# KN-CON.net
KiCad netlist of a schematic drawn in EAGLE
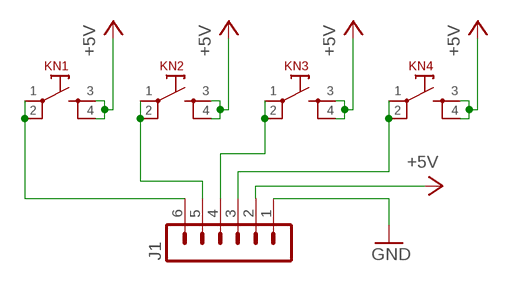
[diagram p0: schematic, sheet 1]

(export (version "E")
  (design (tool "Eeschema 10.0.6"))
  (components
    (comp (ref "J1")
      (value "MA06-1")
      (footprint "eagle-import:MA06-1")
      (libsource (lib "eagle-import") (part "MA06-1"))
    )
    (comp (ref "KN1")
      (value "LZQ-KN")
      (footprint "eagle-import:LZQ-KN")
      (libsource (lib "eagle-import") (part "LZQ-KN"))
    )
    (comp (ref "KN2")
      (value "LZQ-KN")
      (footprint "eagle-import:LZQ-KN")
      (libsource (lib "eagle-import") (part "LZQ-KN"))
    )
    (comp (ref "KN3")
      (value "LZQ-KN")
      (footprint "eagle-import:LZQ-KN")
      (libsource (lib "eagle-import") (part "LZQ-KN"))
    )
    (comp (ref "KN4")
      (value "LZQ-KN")
      (footprint "eagle-import:LZQ-KN")
      (libsource (lib "eagle-import") (part "LZQ-KN"))
    )
  )
  (nets
    (net (code "1") (name "+5V") (class "Default")
      (node (ref "J1") (pin "2") (pinfunction "2_2") (pintype "passive"))
      (node (ref "KN1") (pin "3") (pinfunction "3_3") (pintype "bidirectional"))
      (node (ref "KN1") (pin "4") (pinfunction "4_4") (pintype "bidirectional"))
      (node (ref "KN2") (pin "3") (pinfunction "3_3") (pintype "bidirectional"))
      (node (ref "KN2") (pin "4") (pinfunction "4_4") (pintype "bidirectional"))
      (node (ref "KN3") (pin "3") (pinfunction "3_3") (pintype "bidirectional"))
      (node (ref "KN3") (pin "4") (pinfunction "4_4") (pintype "bidirectional"))
      (node (ref "KN4") (pin "3") (pinfunction "3_3") (pintype "bidirectional"))
      (node (ref "KN4") (pin "4") (pinfunction "4_4") (pintype "bidirectional"))
    )
    (net (code "2") (name "GND") (class "Default")
      (node (ref "J1") (pin "1") (pinfunction "1_1") (pintype "passive"))
    )
    (net (code "3") (name "Net-(J1-Pad3)") (class "Default")
      (node (ref "J1") (pin "3") (pinfunction "3_3") (pintype "passive"))
      (node (ref "KN4") (pin "1") (pinfunction "1_1") (pintype "bidirectional"))
      (node (ref "KN4") (pin "2") (pinfunction "2_2") (pintype "bidirectional"))
    )
    (net (code "4") (name "Net-(J1-Pad4)") (class "Default")
      (node (ref "J1") (pin "4") (pinfunction "4_4") (pintype "passive"))
      (node (ref "KN3") (pin "1") (pinfunction "1_1") (pintype "bidirectional"))
      (node (ref "KN3") (pin "2") (pinfunction "2_2") (pintype "bidirectional"))
    )
    (net (code "5") (name "Net-(J1-Pad5)") (class "Default")
      (node (ref "J1") (pin "5") (pinfunction "5_5") (pintype "passive"))
      (node (ref "KN2") (pin "1") (pinfunction "1_1") (pintype "bidirectional"))
      (node (ref "KN2") (pin "2") (pinfunction "2_2") (pintype "bidirectional"))
    )
    (net (code "6") (name "Net-(J1-Pad6)") (class "Default")
      (node (ref "J1") (pin "6") (pinfunction "6_6") (pintype "passive"))
      (node (ref "KN1") (pin "1") (pinfunction "1_1") (pintype "bidirectional"))
      (node (ref "KN1") (pin "2") (pinfunction "2_2") (pintype "bidirectional"))
    )
  )
)
